# Constant_Current_schematic_2022-05-03.net
KiCad netlist of a schematic drawn in Altium Designer
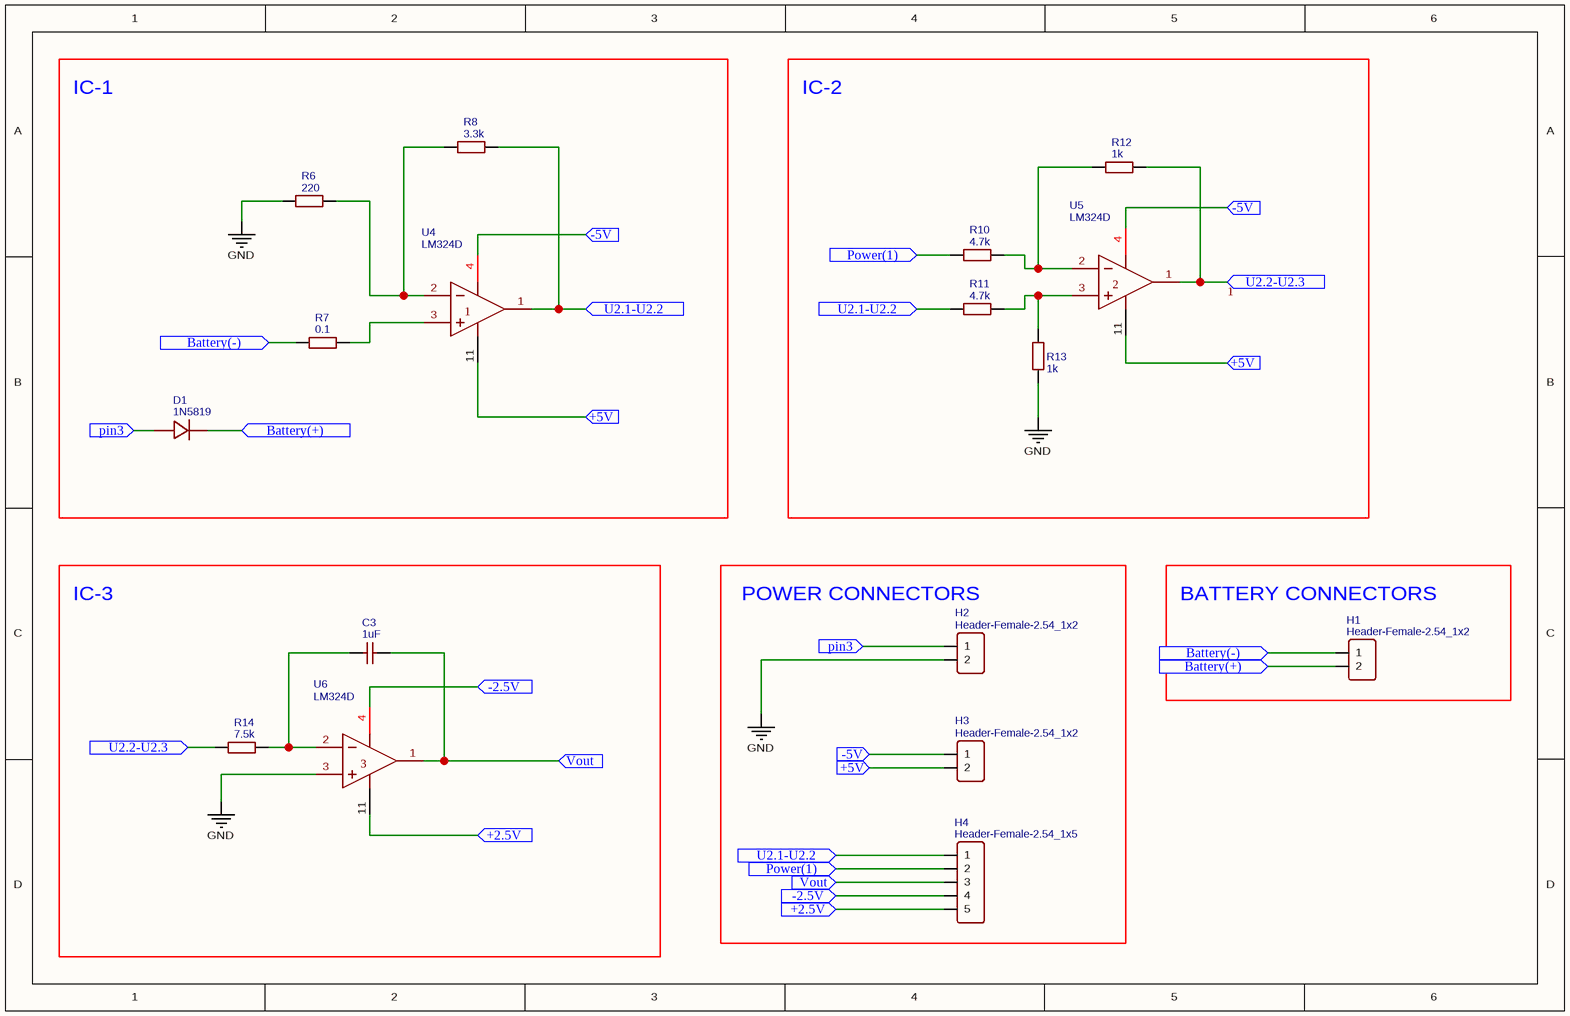
[diagram p0: Constant_Current_schematic_2022-05-03.schdoc]

(export (version "E")
  (design (tool "Eeschema 10.0.6"))
  (components
    (comp (ref "C3")
      (value "1uF")
      (fields
        (field (name "BOM_MANUFACTURER PART") "22pf/50V 10%")
        (field (name "BOM_SUPPLIER PART") "C9316")
      )
      (libsource (lib "altium-import") (part "root_0_1uF_"))
    )
    (comp (ref "D1")
      (value "1N5819")
      (fields (field (name "BOM_SUPPLIER PART") "C256527") (field (name "CONTRIBUTOR") "LCSC"))
      (libsource (lib "altium-import") (part "root_2_1N5819_"))
    )
    (comp (ref "H1")
      (value "Header-Female-2.54_1x2")
      (fields
        (field (name "BOM_MANUFACTURER PART") "2.54-1*2PFemale")
        (field (name "BOM_SUPPLIER PART") "C49661")
      )
      (libsource (lib "altium-import") (part "root_0_Header-Female-2.54_1x2_"))
    )
    (comp (ref "H2")
      (value "Header-Female-2.54_1x2")
      (fields
        (field (name "BOM_MANUFACTURER PART") "2.54-1*2PFemale")
        (field (name "BOM_SUPPLIER PART") "C49661")
      )
      (libsource (lib "altium-import") (part "root_0_Header-Female-2.54_1x2_"))
    )
    (comp (ref "H3")
      (value "Header-Female-2.54_1x2")
      (fields
        (field (name "BOM_MANUFACTURER PART") "2.54-1*2PFemale")
        (field (name "BOM_SUPPLIER PART") "C49661")
      )
      (libsource (lib "altium-import") (part "root_0_Header-Female-2.54_1x2_"))
    )
    (comp (ref "H4")
      (value "Header-Female-2.54_1x5")
      (fields
        (field (name "BOM_MANUFACTURER PART") "2.54mm 1*5p Female header")
        (field (name "BOM_SUPPLIER PART") "C50950")
      )
      (libsource (lib "altium-import") (part "root_0_Header-Female-2.54_1x5_"))
    )
    (comp (ref "R6")
      (value "220")
      (fields
        (field (name "POWER") "1/4W")
        (field (name "TOLERANCE") "±1%")
        (field (name "BOM_SUPPLIER PART") "E57439")
      )
      (libsource (lib "altium-import") (part "root_0_220_"))
    )
    (comp (ref "R7")
      (value "0.1")
      (fields
        (field (name "POWER") "1/4W")
        (field (name "TOLERANCE") "±1%")
        (field (name "BOM_SUPPLIER PART") "E57439")
      )
      (libsource (lib "altium-import") (part "root_0_0.1_"))
    )
    (comp (ref "R8")
      (value "3.3k")
      (fields
        (field (name "POWER") "1/4W")
        (field (name "TOLERANCE") "±1%")
        (field (name "BOM_SUPPLIER PART") "E57439")
      )
      (libsource (lib "altium-import") (part "root_0_3.3k_"))
    )
    (comp (ref "R10")
      (value "4.7k")
      (fields
        (field (name "POWER") "1/4W")
        (field (name "TOLERANCE") "±1%")
        (field (name "BOM_SUPPLIER PART") "E57439")
      )
      (libsource (lib "altium-import") (part "root_0_4.7k_"))
    )
    (comp (ref "R11")
      (value "4.7k")
      (fields
        (field (name "POWER") "1/4W")
        (field (name "TOLERANCE") "±1%")
        (field (name "BOM_SUPPLIER PART") "E57439")
      )
      (libsource (lib "altium-import") (part "root_0_4.7k_"))
    )
    (comp (ref "R12")
      (value "1k")
      (fields
        (field (name "POWER") "1/4W")
        (field (name "TOLERANCE") "±1%")
        (field (name "BOM_SUPPLIER PART") "E57439")
      )
      (libsource (lib "altium-import") (part "root_0_1k_"))
    )
    (comp (ref "R13")
      (value "1k")
      (fields
        (field (name "POWER") "1/4W")
        (field (name "TOLERANCE") "±1%")
        (field (name "BOM_SUPPLIER PART") "E57439")
      )
      (libsource (lib "altium-import") (part "root_1_1k_"))
    )
    (comp (ref "R14")
      (value "7.5k")
      (fields
        (field (name "POWER") "1/4W")
        (field (name "TOLERANCE") "±1%")
        (field (name "BOM_SUPPLIER PART") "E57439")
      )
      (libsource (lib "altium-import") (part "root_0_7.5k_"))
    )
    (comp (ref "U4")
      (value "LM324D")
      (fields
        (field (name "BOM_SUPPLIER PART") "C2935189")
        (field (name "SUBPART_NO") "1")
        (field (name "CONTRIBUTOR") "LCSC")
      )
      (libsource (lib "altium-import") (part "root_0_LM324D_"))
    )
    (comp (ref "U5")
      (value "LM324D")
      (fields
        (field (name "BOM_SUPPLIER PART") "C2935189")
        (field (name "SUBPART_NO") "1")
        (field (name "CONTRIBUTOR") "LCSC")
      )
      (libsource (lib "altium-import") (part "root_0_LM324D_"))
    )
    (comp (ref "U6")
      (value "LM324D")
      (fields
        (field (name "BOM_SUPPLIER PART") "C2935189")
        (field (name "SUBPART_NO") "1")
        (field (name "CONTRIBUTOR") "LCSC")
      )
      (libsource (lib "altium-import") (part "root_0_LM324D_"))
    )
  )
  (nets
    (net (code "1") (name "/+2.5V") (class "Default")
      (node (ref "H4") (pin "5") (pinfunction "5_5") (pintype "passive"))
      (node (ref "U6") (pin "11") (pinfunction "VCC-_11") (pintype "passive"))
    )
    (net (code "2") (name "/+5V") (class "Default")
      (node (ref "H3") (pin "2") (pinfunction "2_2") (pintype "passive"))
      (node (ref "U4") (pin "11") (pinfunction "VCC-_11") (pintype "passive"))
      (node (ref "U5") (pin "11") (pinfunction "VCC-_11") (pintype "passive"))
    )
    (net (code "3") (name "/-2.5V") (class "Default")
      (node (ref "H4") (pin "4") (pinfunction "4_4") (pintype "passive"))
      (node (ref "U6") (pin "4") (pinfunction "VCC+_4") (pintype "passive"))
    )
    (net (code "4") (name "/-5V") (class "Default")
      (node (ref "H3") (pin "1") (pinfunction "1_1") (pintype "passive"))
      (node (ref "U4") (pin "4") (pinfunction "VCC+_4") (pintype "passive"))
      (node (ref "U5") (pin "4") (pinfunction "VCC+_4") (pintype "passive"))
    )
    (net (code "5") (name "/Battery(+)") (class "Default")
      (node (ref "D1") (pin "1") (pinfunction "K_1") (pintype "passive"))
      (node (ref "H1") (pin "2") (pinfunction "2_2") (pintype "passive"))
    )
    (net (code "6") (name "/Battery(-)") (class "Default")
      (node (ref "H1") (pin "1") (pinfunction "1_1") (pintype "passive"))
      (node (ref "R7") (pin "1") (pinfunction "1_1") (pintype "passive"))
    )
    (net (code "7") (name "/Power(1)") (class "Default")
      (node (ref "H4") (pin "2") (pinfunction "2_2") (pintype "passive"))
      (node (ref "R10") (pin "1") (pinfunction "1_1") (pintype "passive"))
    )
    (net (code "8") (name "/U2.1-U2.2") (class "Default")
      (node (ref "H4") (pin "1") (pinfunction "1_1") (pintype "passive"))
      (node (ref "R11") (pin "1") (pinfunction "1_1") (pintype "passive"))
      (node (ref "R8") (pin "2") (pinfunction "2_2") (pintype "passive"))
      (node (ref "U4") (pin "1") (pinfunction "OUT1_1") (pintype "passive"))
    )
    (net (code "9") (name "/U2.2-U2.3") (class "Default")
      (node (ref "R12") (pin "2") (pinfunction "2_2") (pintype "passive"))
      (node (ref "R14") (pin "1") (pinfunction "1_1") (pintype "passive"))
      (node (ref "U5") (pin "1") (pinfunction "OUT1_1") (pintype "passive"))
    )
    (net (code "10") (name "/Vout") (class "Default")
      (node (ref "C3") (pin "2") (pinfunction "2_2") (pintype "passive"))
      (node (ref "H4") (pin "3") (pinfunction "3_3") (pintype "passive"))
      (node (ref "U6") (pin "1") (pinfunction "OUT1_1") (pintype "passive"))
    )
    (net (code "11") (name "/pin3") (class "Default")
      (node (ref "D1") (pin "2") (pinfunction "A_2") (pintype "passive"))
      (node (ref "H2") (pin "1") (pinfunction "1_1") (pintype "passive"))
    )
    (net (code "12") (name "GND") (class "Default")
      (node (ref "H2") (pin "2") (pinfunction "2_2") (pintype "passive"))
      (node (ref "R13") (pin "1") (pinfunction "1_1") (pintype "passive"))
      (node (ref "R6") (pin "1") (pinfunction "1_1") (pintype "passive"))
      (node (ref "U6") (pin "3") (pinfunction "IN1+_3") (pintype "passive"))
    )
    (net (code "13") (name "Net-(U4-IN1+)") (class "Default")
      (node (ref "R7") (pin "2") (pinfunction "2_2") (pintype "passive"))
      (node (ref "U4") (pin "3") (pinfunction "IN1+_3") (pintype "passive"))
    )
    (net (code "14") (name "Net-(U4-IN1-)") (class "Default")
      (node (ref "R6") (pin "2") (pinfunction "2_2") (pintype "passive"))
      (node (ref "R8") (pin "1") (pinfunction "1_1") (pintype "passive"))
      (node (ref "U4") (pin "2") (pinfunction "IN1-_2") (pintype "passive"))
    )
    (net (code "15") (name "Net-(U5-IN1+)") (class "Default")
      (node (ref "R11") (pin "2") (pinfunction "2_2") (pintype "passive"))
      (node (ref "R13") (pin "2") (pinfunction "2_2") (pintype "passive"))
      (node (ref "U5") (pin "3") (pinfunction "IN1+_3") (pintype "passive"))
    )
    (net (code "16") (name "Net-(U5-IN1-)") (class "Default")
      (node (ref "R10") (pin "2") (pinfunction "2_2") (pintype "passive"))
      (node (ref "R12") (pin "1") (pinfunction "1_1") (pintype "passive"))
      (node (ref "U5") (pin "2") (pinfunction "IN1-_2") (pintype "passive"))
    )
    (net (code "17") (name "Net-(U6-IN1-)") (class "Default")
      (node (ref "C3") (pin "1") (pinfunction "1_1") (pintype "passive"))
      (node (ref "R14") (pin "2") (pinfunction "2_2") (pintype "passive"))
      (node (ref "U6") (pin "2") (pinfunction "IN1-_2") (pintype "passive"))
    )
  )
)
